# TPS54528.net
KiCad netlist of a schematic drawn in Altium Designer
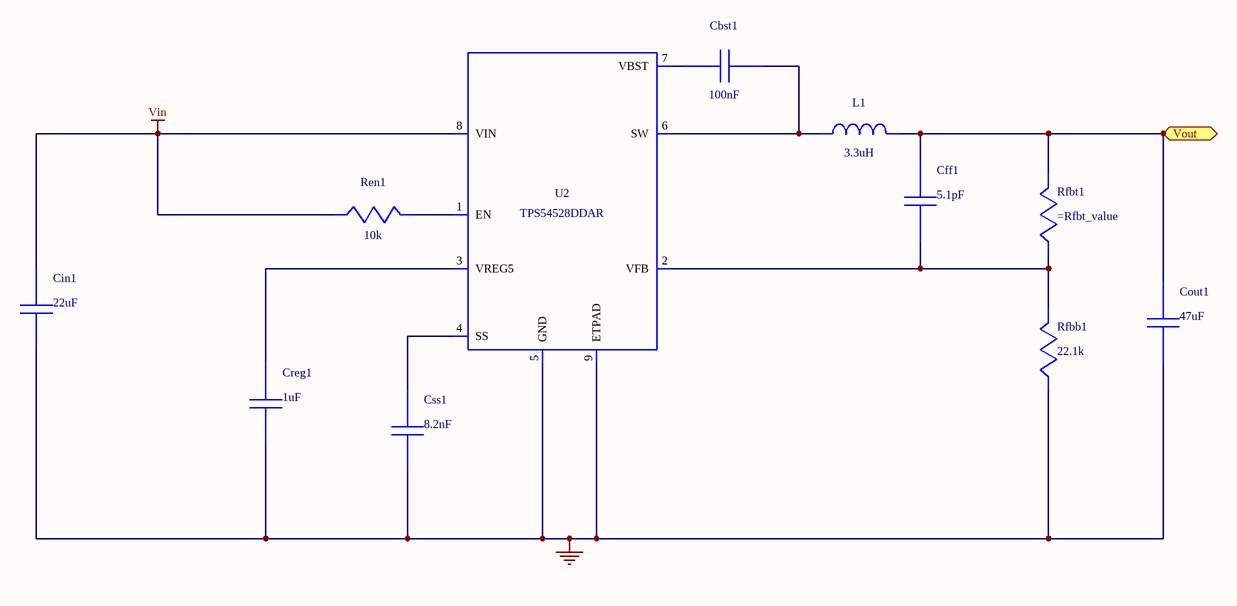
[diagram p0: TPS54528.schdoc]

(export (version "E")
  (design (tool "Eeschema 10.0.6"))
  (components
    (comp (ref "Cbst1")
      (value "100nF")
      (footprint "AXIAL-0.3")
      (description "C1005X5R1A104K")
      (libsource (lib "TI WEBENCH") (part "Cbst"))
    )
    (comp (ref "Cff1")
      (value "5.1pF")
      (footprint "AXIAL-0.3")
      (description "GRM1555C1E5R1CA0")
      (fields (field (name "MANUFACTURER PART NUMBER") "GRM1555C1E5R1CA01D"))
      (libsource (lib "TI WEBENCH") (part "Cff"))
    )
    (comp (ref "Cin1")
      (value "22uF")
      (footprint "AXIAL-0.3")
      (description "GRM32ER61E226KE1")
      (fields (field (name "MANUFACTURER PART NUMBER") "GRM32ER61E226KE15L"))
      (libsource (lib "TI WEBENCH") (part "Cin"))
    )
    (comp (ref "Cout1")
      (value "47uF")
      (footprint "AXIAL-0.3")
      (description "GRM31CR61A476KE1")
      (fields (field (name "MANUFACTURER PART NUMBER") "GRM31CR61A476KE15L"))
      (libsource (lib "TI WEBENCH") (part "Cout"))
    )
    (comp (ref "Creg1")
      (value "1uF")
      (footprint "AXIAL-0.3")
      (description "C1608X5R1A105K")
      (libsource (lib "TI WEBENCH") (part "Creg"))
    )
    (comp (ref "Css1")
      (value "8.2nF")
      (footprint "AXIAL-0.3")
      (description "GRM155R71E822KA0")
      (fields (field (name "MANUFACTURER PART NUMBER") "GRM155R71E822KA01D"))
      (libsource (lib "TI WEBENCH") (part "Css"))
    )
    (comp (ref "L1")
      (value "3.3uH")
      (footprint "Inductor")
      (description "Unknown")
      (fields (field (name "MANUFACTURER PART NUMBER") "IHLP3232DZER3R3M11"))
      (libsource (lib "TI WEBENCH") (part "L1"))
    )
    (comp (ref "Ren1")
      (value "10k")
      (footprint "AXIAL-0.3")
      (description "CRCW040210K0FKED")
      (libsource (lib "TI WEBENCH") (part "Ren"))
    )
    (comp (ref "Rfbb1")
      (value "22.1k")
      (footprint "AXIAL-0.3")
      (description "CRCW040222K1FKED")
      (libsource (lib "TI WEBENCH") (part "Rfbb"))
    )
    (comp (ref "Rfbt1")
      (value "CRCW0402121KFKED")
      (footprint "AXIAL-0.3")
      (libsource (lib "TI WEBENCH") (part "Rfbt"))
    )
    (comp (ref "U2")
      (value "TPS54528DDAR")
      (footprint "DDA8_3P1X2P4")
      (fields (field (name "PACKAGEREFERENCE") "TPS54528DDAR"))
      (libsource (lib "TI WEBENCH") (part "U1"))
    )
  )
  (nets
    (net (code "1") (name "/Vout") (class "Default")
      (node (ref "Cff1") (pin "1") (pinfunction "1_1") (pintype "passive"))
      (node (ref "Cout1") (pin "1") (pinfunction "1_1") (pintype "passive"))
      (node (ref "L1") (pin "2") (pinfunction "2_2") (pintype "passive"))
      (node (ref "Rfbt1") (pin "1") (pinfunction "1_1") (pintype "passive"))
    )
    (net (code "2") (name "GND") (class "Default")
      (node (ref "Cin1") (pin "2") (pinfunction "2_2") (pintype "passive"))
      (node (ref "Cout1") (pin "2") (pinfunction "2_2") (pintype "passive"))
      (node (ref "Creg1") (pin "2") (pinfunction "2_2") (pintype "passive"))
      (node (ref "Css1") (pin "2") (pinfunction "2_2") (pintype "passive"))
      (node (ref "Rfbb1") (pin "2") (pinfunction "2_2") (pintype "passive"))
      (node (ref "U2") (pin "5") (pinfunction "GND_5") (pintype "passive"))
      (node (ref "U2") (pin "9") (pinfunction "ETPAD_9") (pintype "passive"))
    )
    (net (code "3") (name "Net-(U2-EN)") (class "Default")
      (node (ref "Ren1") (pin "1") (pinfunction "1_1") (pintype "passive"))
      (node (ref "U2") (pin "1") (pinfunction "EN_1") (pintype "passive"))
    )
    (net (code "4") (name "Net-(U2-SS)") (class "Default")
      (node (ref "Css1") (pin "1") (pinfunction "1_1") (pintype "passive"))
      (node (ref "U2") (pin "4") (pinfunction "SS_4") (pintype "passive"))
    )
    (net (code "5") (name "Net-(U2-SW)") (class "Default")
      (node (ref "Cbst1") (pin "2") (pinfunction "2_2") (pintype "passive"))
      (node (ref "L1") (pin "1") (pinfunction "1_1") (pintype "passive"))
      (node (ref "U2") (pin "6") (pinfunction "SW_6") (pintype "passive"))
    )
    (net (code "6") (name "Net-(U2-VBST)") (class "Default")
      (node (ref "Cbst1") (pin "1") (pinfunction "1_1") (pintype "passive"))
      (node (ref "U2") (pin "7") (pinfunction "VBST_7") (pintype "passive"))
    )
    (net (code "7") (name "Net-(U2-VFB)") (class "Default")
      (node (ref "Cff1") (pin "2") (pinfunction "2_2") (pintype "passive"))
      (node (ref "Rfbb1") (pin "1") (pinfunction "1_1") (pintype "passive"))
      (node (ref "Rfbt1") (pin "2") (pinfunction "2_2") (pintype "passive"))
      (node (ref "U2") (pin "2") (pinfunction "VFB_2") (pintype "passive"))
    )
    (net (code "8") (name "Net-(U2-VREG5)") (class "Default")
      (node (ref "Creg1") (pin "1") (pinfunction "1_1") (pintype "passive"))
      (node (ref "U2") (pin "3") (pinfunction "VREG5_3") (pintype "passive"))
    )
    (net (code "9") (name "Vin") (class "Default")
      (node (ref "Cin1") (pin "1") (pinfunction "1_1") (pintype "passive"))
      (node (ref "Ren1") (pin "2") (pinfunction "2_2") (pintype "passive"))
      (node (ref "U2") (pin "8") (pinfunction "VIN_8") (pintype "passive"))
    )
  )
)
